# Controllable_voltage_outputs.net
KiCad netlist of a schematic drawn in Altium Designer
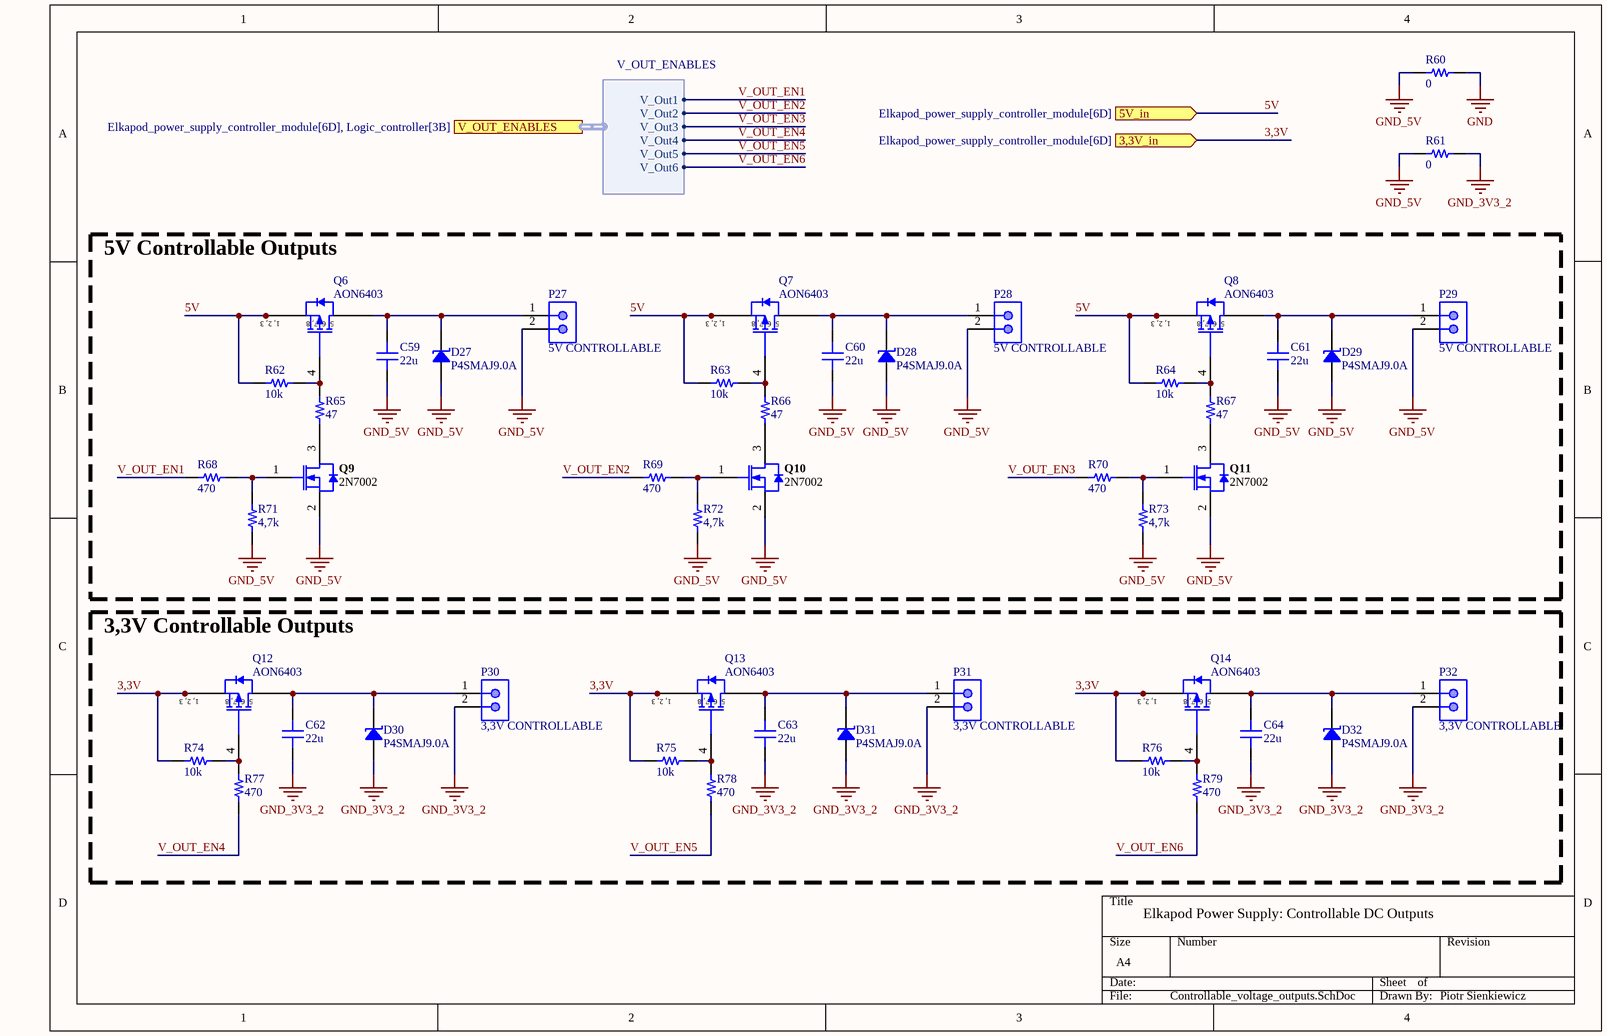
[diagram p0: Controllable_voltage_outputs.SchDoc]

(export (version "E")
  (design (tool "Eeschema 10.0.6"))
  (components
    (comp (ref "C59")
      (value "22u")
      (footprint "CAP 0805_2012")
      (description "CAP CER 22UF 25V X7R 0805")
      (fields
        (field (name "PART NUMBER") "VJ0805Y684KXQTW1BC")
        (field (name "MANUFACTURER") "Vishay Vitramon")
      )
      (libsource (lib "Celestial Altium Library - altium_library") (part "Capacitor"))
    )
    (comp (ref "C60")
      (value "22u")
      (footprint "CAP 0805_2012")
      (description "CAP CER 22UF 25V X7R 0805")
      (fields
        (field (name "PART NUMBER") "VJ0805Y684KXQTW1BC")
        (field (name "MANUFACTURER") "Vishay Vitramon")
      )
      (libsource (lib "Celestial Altium Library - altium_library") (part "Capacitor"))
    )
    (comp (ref "C61")
      (value "22u")
      (footprint "CAP 0805_2012")
      (description "CAP CER 22UF 25V X7R 0805")
      (fields
        (field (name "PART NUMBER") "VJ0805Y684KXQTW1BC")
        (field (name "MANUFACTURER") "Vishay Vitramon")
      )
      (libsource (lib "Celestial Altium Library - altium_library") (part "Capacitor"))
    )
    (comp (ref "C62")
      (value "22u")
      (footprint "CAP 0805_2012")
      (description "CAP CER 22UF 25V X7R 0805")
      (fields
        (field (name "PART NUMBER") "VJ0805Y684KXQTW1BC")
        (field (name "MANUFACTURER") "Vishay Vitramon")
      )
      (libsource (lib "Celestial Altium Library - altium_library") (part "Capacitor"))
    )
    (comp (ref "C63")
      (value "22u")
      (footprint "CAP 0805_2012")
      (description "CAP CER 22UF 25V X7R 0805")
      (fields
        (field (name "PART NUMBER") "VJ0805Y684KXQTW1BC")
        (field (name "MANUFACTURER") "Vishay Vitramon")
      )
      (libsource (lib "Celestial Altium Library - altium_library") (part "Capacitor"))
    )
    (comp (ref "C64")
      (value "22u")
      (footprint "CAP 0805_2012")
      (description "CAP CER 22UF 25V X7R 0805")
      (fields
        (field (name "PART NUMBER") "VJ0805Y684KXQTW1BC")
        (field (name "MANUFACTURER") "Vishay Vitramon")
      )
      (libsource (lib "Celestial Altium Library - altium_library") (part "Capacitor"))
    )
    (comp (ref "D27")
      (value "P4SMAJ9.0A")
      (footprint "DO214AC SMA")
      (description "TVS DIODE 9VDC DO214AC")
      (libsource (lib "Celestial Altium Library - altium_library") (part "DIODE TVS UNI"))
    )
    (comp (ref "D28")
      (value "P4SMAJ9.0A")
      (footprint "DO214AC SMA")
      (description "TVS DIODE 9VDC DO214AC")
      (libsource (lib "Celestial Altium Library - altium_library") (part "DIODE TVS UNI"))
    )
    (comp (ref "D29")
      (value "P4SMAJ9.0A")
      (footprint "DO214AC SMA")
      (description "TVS DIODE 9VDC DO214AC")
      (libsource (lib "Celestial Altium Library - altium_library") (part "DIODE TVS UNI"))
    )
    (comp (ref "D30")
      (value "P4SMAJ9.0A")
      (footprint "DO214AC SMA")
      (description "TVS DIODE 9VDC DO214AC")
      (libsource (lib "Celestial Altium Library - altium_library") (part "DIODE TVS UNI"))
    )
    (comp (ref "D31")
      (value "P4SMAJ9.0A")
      (footprint "DO214AC SMA")
      (description "TVS DIODE 9VDC DO214AC")
      (libsource (lib "Celestial Altium Library - altium_library") (part "DIODE TVS UNI"))
    )
    (comp (ref "D32")
      (value "P4SMAJ9.0A")
      (footprint "DO214AC SMA")
      (description "TVS DIODE 9VDC DO214AC")
      (libsource (lib "Celestial Altium Library - altium_library") (part "DIODE TVS UNI"))
    )
    (comp (ref "P27")
      (value "5V CONTROLLABLE")
      (footprint "MOLX-22-23-2021_V")
      (fields (field (name "PARTNUMBER") "22-23-2021"))
      (libsource (lib "Altium Content Vault") (part "CN-1P-M-R2"))
    )
    (comp (ref "P28")
      (value "5V CONTROLLABLE")
      (footprint "MOLX-22-23-2021_V")
      (fields (field (name "PARTNUMBER") "22-23-2021"))
      (libsource (lib "Altium Content Vault") (part "CN-1P-M-R2"))
    )
    (comp (ref "P29")
      (value "5V CONTROLLABLE")
      (footprint "MOLX-22-23-2021_V")
      (fields (field (name "PARTNUMBER") "22-23-2021"))
      (libsource (lib "Altium Content Vault") (part "CN-1P-M-R2"))
    )
    (comp (ref "P30")
      (value "3,3V CONTROLLABLE")
      (footprint "MOLX-22-23-2021_V")
      (fields (field (name "PARTNUMBER") "22-23-2021"))
      (libsource (lib "Altium Content Vault") (part "CN-1P-M-R2"))
    )
    (comp (ref "P31")
      (value "3,3V CONTROLLABLE")
      (footprint "MOLX-22-23-2021_V")
      (fields (field (name "PARTNUMBER") "22-23-2021"))
      (libsource (lib "Altium Content Vault") (part "CN-1P-M-R2"))
    )
    (comp (ref "P32")
      (value "3,3V CONTROLLABLE")
      (footprint "MOLX-22-23-2021_V")
      (fields (field (name "PARTNUMBER") "22-23-2021"))
      (libsource (lib "Altium Content Vault") (part "CN-1P-M-R2"))
    )
    (comp (ref "Q6")
      (value "AON6403")
      (footprint "DFN5x6")
      (description "P-MOSFET; 67A; 30V; DFN5x6")
      (libsource (lib "My_transistors") (part "AON6403"))
    )
    (comp (ref "Q7")
      (value "AON6403")
      (footprint "DFN5x6")
      (description "P-MOSFET; 67A; 30V; DFN5x6")
      (libsource (lib "My_transistors") (part "AON6403"))
    )
    (comp (ref "Q8")
      (value "AON6403")
      (footprint "DFN5x6")
      (description "P-MOSFET; 67A; 30V; DFN5x6")
      (libsource (lib "My_transistors") (part "AON6403"))
    )
    (comp (ref "Q9")
      (value "2N7002")
      (footprint "INF-PG-SOT23_M")
      (fields (field (name "MANUFACTURER") "Infineon"))
      (libsource (lib "Altium Content Vault") (part "INF-NDMOS-GSD-3"))
    )
    (comp (ref "Q10")
      (value "2N7002")
      (footprint "INF-PG-SOT23_M")
      (fields (field (name "MANUFACTURER") "Infineon"))
      (libsource (lib "Altium Content Vault") (part "INF-NDMOS-GSD-3"))
    )
    (comp (ref "Q11")
      (value "2N7002")
      (footprint "INF-PG-SOT23_M")
      (fields (field (name "MANUFACTURER") "Infineon"))
      (libsource (lib "Altium Content Vault") (part "INF-NDMOS-GSD-3"))
    )
    (comp (ref "Q12")
      (value "AON6403")
      (footprint "DFN5x6")
      (description "P-MOSFET; 67A; 30V; DFN5x6")
      (libsource (lib "My_transistors") (part "AON6403"))
    )
    (comp (ref "Q13")
      (value "AON6403")
      (footprint "DFN5x6")
      (description "P-MOSFET; 67A; 30V; DFN5x6")
      (libsource (lib "My_transistors") (part "AON6403"))
    )
    (comp (ref "Q14")
      (value "AON6403")
      (footprint "DFN5x6")
      (description "P-MOSFET; 67A; 30V; DFN5x6")
      (libsource (lib "My_transistors") (part "AON6403"))
    )
    (comp (ref "R60")
      (value "0")
      (footprint "RES 0603_1608")
      (description "RES 0 OHM 1% 0,1W 0603")
      (fields
        (field (name "PART NUMBER") "RNCS0603BKE10K0")
        (field (name "MANUFACTURER") "Stackpole Electronics Inc")
      )
      (libsource (lib "Celestial Altium Library - altium_library") (part "Resistor"))
    )
    (comp (ref "R61")
      (value "0")
      (footprint "RES 0603_1608")
      (description "RES 0 OHM 1% 0,1W 0603")
      (fields
        (field (name "PART NUMBER") "RNCS0603BKE10K0")
        (field (name "MANUFACTURER") "Stackpole Electronics Inc")
      )
      (libsource (lib "Celestial Altium Library - altium_library") (part "Resistor"))
    )
    (comp (ref "R62")
      (value "10k")
      (footprint "RES 0603_1608")
      (description "RES 10K OHM 1% 0,1W 0603")
      (fields
        (field (name "PART NUMBER") "RNCS0603BKE10K0")
        (field (name "MANUFACTURER") "Stackpole Electronics Inc")
      )
      (libsource (lib "Celestial Altium Library - altium_library") (part "Resistor"))
    )
    (comp (ref "R63")
      (value "10k")
      (footprint "RES 0603_1608")
      (description "RES 10K OHM 1% 0,1W 0603")
      (fields
        (field (name "PART NUMBER") "RNCS0603BKE10K0")
        (field (name "MANUFACTURER") "Stackpole Electronics Inc")
      )
      (libsource (lib "Celestial Altium Library - altium_library") (part "Resistor"))
    )
    (comp (ref "R64")
      (value "10k")
      (footprint "RES 0603_1608")
      (description "RES 10K OHM 1% 0,1W 0603")
      (fields
        (field (name "PART NUMBER") "RNCS0603BKE10K0")
        (field (name "MANUFACTURER") "Stackpole Electronics Inc")
      )
      (libsource (lib "Celestial Altium Library - altium_library") (part "Resistor"))
    )
    (comp (ref "R65")
      (value "47")
      (footprint "RES 0603_1608")
      (description "RES 47 OHM 1% 0,1W 0603")
      (fields
        (field (name "PART NUMBER") "RNCS0603BKE10K0")
        (field (name "MANUFACTURER") "Stackpole Electronics Inc")
      )
      (libsource (lib "Celestial Altium Library - altium_library") (part "Resistor"))
    )
    (comp (ref "R66")
      (value "47")
      (footprint "RES 0603_1608")
      (description "RES 47 OHM 1% 0,1W 0603")
      (fields
        (field (name "PART NUMBER") "RNCS0603BKE10K0")
        (field (name "MANUFACTURER") "Stackpole Electronics Inc")
      )
      (libsource (lib "Celestial Altium Library - altium_library") (part "Resistor"))
    )
    (comp (ref "R67")
      (value "47")
      (footprint "RES 0603_1608")
      (description "RES 47 OHM 1% 0,1W 0603")
      (fields
        (field (name "PART NUMBER") "RNCS0603BKE10K0")
        (field (name "MANUFACTURER") "Stackpole Electronics Inc")
      )
      (libsource (lib "Celestial Altium Library - altium_library") (part "Resistor"))
    )
    (comp (ref "R68")
      (value "470")
      (footprint "RES 0603_1608")
      (description "RES 470 OHM 1% 0,1W 0603")
      (fields
        (field (name "PART NUMBER") "RNCS0603BKE10K0")
        (field (name "MANUFACTURER") "Stackpole Electronics Inc")
      )
      (libsource (lib "Celestial Altium Library - altium_library") (part "Resistor"))
    )
    (comp (ref "R69")
      (value "470")
      (footprint "RES 0603_1608")
      (description "RES 470 OHM 1% 0,1W 0603")
      (fields
        (field (name "PART NUMBER") "RNCS0603BKE10K0")
        (field (name "MANUFACTURER") "Stackpole Electronics Inc")
      )
      (libsource (lib "Celestial Altium Library - altium_library") (part "Resistor"))
    )
    (comp (ref "R70")
      (value "470")
      (footprint "RES 0603_1608")
      (description "RES 470 OHM 1% 0,1W 0603")
      (fields
        (field (name "PART NUMBER") "RNCS0603BKE10K0")
        (field (name "MANUFACTURER") "Stackpole Electronics Inc")
      )
      (libsource (lib "Celestial Altium Library - altium_library") (part "Resistor"))
    )
    (comp (ref "R71")
      (value "4,7k")
      (footprint "RES 0603_1608")
      (description "RES 4,7K OHM 1% 0,1W 0603")
      (fields
        (field (name "PART NUMBER") "RNCS0603BKE10K0")
        (field (name "MANUFACTURER") "Stackpole Electronics Inc")
      )
      (libsource (lib "Celestial Altium Library - altium_library") (part "Resistor"))
    )
    (comp (ref "R72")
      (value "4,7k")
      (footprint "RES 0603_1608")
      (description "RES 4,7K OHM 1% 0,1W 0603")
      (fields
        (field (name "PART NUMBER") "RNCS0603BKE10K0")
        (field (name "MANUFACTURER") "Stackpole Electronics Inc")
      )
      (libsource (lib "Celestial Altium Library - altium_library") (part "Resistor"))
    )
    (comp (ref "R73")
      (value "4,7k")
      (footprint "RES 0603_1608")
      (description "RES 4,7K OHM 1% 0,1W 0603")
      (fields
        (field (name "PART NUMBER") "RNCS0603BKE10K0")
        (field (name "MANUFACTURER") "Stackpole Electronics Inc")
      )
      (libsource (lib "Celestial Altium Library - altium_library") (part "Resistor"))
    )
    (comp (ref "R74")
      (value "10k")
      (footprint "RES 0603_1608")
      (description "RES 10K OHM 1% 0,1W 0603")
      (fields
        (field (name "PART NUMBER") "RNCS0603BKE10K0")
        (field (name "MANUFACTURER") "Stackpole Electronics Inc")
      )
      (libsource (lib "Celestial Altium Library - altium_library") (part "Resistor"))
    )
    (comp (ref "R75")
      (value "10k")
      (footprint "RES 0603_1608")
      (description "RES 10K OHM 1% 0,1W 0603")
      (fields
        (field (name "PART NUMBER") "RNCS0603BKE10K0")
        (field (name "MANUFACTURER") "Stackpole Electronics Inc")
      )
      (libsource (lib "Celestial Altium Library - altium_library") (part "Resistor"))
    )
    (comp (ref "R76")
      (value "10k")
      (footprint "RES 0603_1608")
      (description "RES 10K OHM 1% 0,1W 0603")
      (fields
        (field (name "PART NUMBER") "RNCS0603BKE10K0")
        (field (name "MANUFACTURER") "Stackpole Electronics Inc")
      )
      (libsource (lib "Celestial Altium Library - altium_library") (part "Resistor"))
    )
    (comp (ref "R77")
      (value "470")
      (footprint "RES 0603_1608")
      (description "RES 470 OHM 1% 0,1W 0603")
      (fields
        (field (name "PART NUMBER") "RNCS0603BKE10K0")
        (field (name "MANUFACTURER") "Stackpole Electronics Inc")
      )
      (libsource (lib "Celestial Altium Library - altium_library") (part "Resistor"))
    )
    (comp (ref "R78")
      (value "470")
      (footprint "RES 0603_1608")
      (description "RES 470 OHM 1% 0,1W 0603")
      (fields
        (field (name "PART NUMBER") "RNCS0603BKE10K0")
        (field (name "MANUFACTURER") "Stackpole Electronics Inc")
      )
      (libsource (lib "Celestial Altium Library - altium_library") (part "Resistor"))
    )
    (comp (ref "R79")
      (value "470")
      (footprint "RES 0603_1608")
      (description "RES 470 OHM 1% 0,1W 0603")
      (fields
        (field (name "PART NUMBER") "RNCS0603BKE10K0")
        (field (name "MANUFACTURER") "Stackpole Electronics Inc")
      )
      (libsource (lib "Celestial Altium Library - altium_library") (part "Resistor"))
    )
  )
  (nets
    (net (code "2") (name "/3,3V") (class "Default")
      (node (ref "Q12") (pin "1") (pinfunction "S_1") (pintype "passive"))
      (node (ref "Q12") (pin "2") (pinfunction "S_2") (pintype "passive"))
      (node (ref "Q12") (pin "3") (pinfunction "S_3") (pintype "passive"))
      (node (ref "Q13") (pin "1") (pinfunction "S_1") (pintype "passive"))
      (node (ref "Q13") (pin "2") (pinfunction "S_2") (pintype "passive"))
      (node (ref "Q13") (pin "3") (pinfunction "S_3") (pintype "passive"))
      (node (ref "Q14") (pin "1") (pinfunction "S_1") (pintype "passive"))
      (node (ref "Q14") (pin "2") (pinfunction "S_2") (pintype "passive"))
      (node (ref "Q14") (pin "3") (pinfunction "S_3") (pintype "passive"))
      (node (ref "R74") (pin "1") (pinfunction "1_1") (pintype "passive"))
      (node (ref "R75") (pin "1") (pinfunction "1_1") (pintype "passive"))
      (node (ref "R76") (pin "1") (pinfunction "1_1") (pintype "passive"))
    )
    (net (code "3") (name "/5V") (class "Default")
      (node (ref "Q6") (pin "1") (pinfunction "S_1") (pintype "passive"))
      (node (ref "Q6") (pin "2") (pinfunction "S_2") (pintype "passive"))
      (node (ref "Q6") (pin "3") (pinfunction "S_3") (pintype "passive"))
      (node (ref "Q7") (pin "1") (pinfunction "S_1") (pintype "passive"))
      (node (ref "Q7") (pin "2") (pinfunction "S_2") (pintype "passive"))
      (node (ref "Q7") (pin "3") (pinfunction "S_3") (pintype "passive"))
      (node (ref "Q8") (pin "1") (pinfunction "S_1") (pintype "passive"))
      (node (ref "Q8") (pin "2") (pinfunction "S_2") (pintype "passive"))
      (node (ref "Q8") (pin "3") (pinfunction "S_3") (pintype "passive"))
      (node (ref "R62") (pin "1") (pinfunction "1_1") (pintype "passive"))
      (node (ref "R63") (pin "1") (pinfunction "1_1") (pintype "passive"))
      (node (ref "R64") (pin "1") (pinfunction "1_1") (pintype "passive"))
    )
    (net (code "4") (name "/V_OUT_EN1") (class "Default")
      (node (ref "R68") (pin "2") (pinfunction "2_2") (pintype "passive"))
    )
    (net (code "5") (name "/V_OUT_EN2") (class "Default")
      (node (ref "R69") (pin "2") (pinfunction "2_2") (pintype "passive"))
    )
    (net (code "6") (name "/V_OUT_EN3") (class "Default")
      (node (ref "R70") (pin "2") (pinfunction "2_2") (pintype "passive"))
    )
    (net (code "7") (name "/V_OUT_EN4") (class "Default")
      (node (ref "R77") (pin "2") (pinfunction "2_2") (pintype "passive"))
    )
    (net (code "8") (name "/V_OUT_EN5") (class "Default")
      (node (ref "R78") (pin "2") (pinfunction "2_2") (pintype "passive"))
    )
    (net (code "9") (name "/V_OUT_EN6") (class "Default")
      (node (ref "R79") (pin "2") (pinfunction "2_2") (pintype "passive"))
    )
    (net (code "11") (name "GND") (class "Default")
      (node (ref "R60") (pin "2") (pinfunction "2_2") (pintype "passive"))
    )
    (net (code "12") (name "GND_3V3_2") (class "Default")
      (node (ref "C62") (pin "1") (pinfunction "1_1") (pintype "passive"))
      (node (ref "C63") (pin "1") (pinfunction "1_1") (pintype "passive"))
      (node (ref "C64") (pin "1") (pinfunction "1_1") (pintype "passive"))
      (node (ref "D30") (pin "1") (pinfunction "1_1") (pintype "passive"))
      (node (ref "D31") (pin "1") (pinfunction "1_1") (pintype "passive"))
      (node (ref "D32") (pin "1") (pinfunction "1_1") (pintype "passive"))
      (node (ref "P30") (pin "2") (pinfunction "2_2") (pintype "passive"))
      (node (ref "P31") (pin "2") (pinfunction "2_2") (pintype "passive"))
      (node (ref "P32") (pin "2") (pinfunction "2_2") (pintype "passive"))
      (node (ref "R61") (pin "2") (pinfunction "2_2") (pintype "passive"))
    )
    (net (code "13") (name "GND_5V") (class "Default")
      (node (ref "C59") (pin "1") (pinfunction "1_1") (pintype "passive"))
      (node (ref "C60") (pin "1") (pinfunction "1_1") (pintype "passive"))
      (node (ref "C61") (pin "1") (pinfunction "1_1") (pintype "passive"))
      (node (ref "D27") (pin "1") (pinfunction "1_1") (pintype "passive"))
      (node (ref "D28") (pin "1") (pinfunction "1_1") (pintype "passive"))
      (node (ref "D29") (pin "1") (pinfunction "1_1") (pintype "passive"))
      (node (ref "P27") (pin "2") (pinfunction "2_2") (pintype "passive"))
      (node (ref "P28") (pin "2") (pinfunction "2_2") (pintype "passive"))
      (node (ref "P29") (pin "2") (pinfunction "2_2") (pintype "passive"))
      (node (ref "Q10") (pin "2") (pinfunction "SOURCE_2") (pintype "passive"))
      (node (ref "Q11") (pin "2") (pinfunction "SOURCE_2") (pintype "passive"))
      (node (ref "Q9") (pin "2") (pinfunction "SOURCE_2") (pintype "passive"))
      (node (ref "R60") (pin "1") (pinfunction "1_1") (pintype "passive"))
      (node (ref "R61") (pin "1") (pinfunction "1_1") (pintype "passive"))
      (node (ref "R71") (pin "2") (pinfunction "2_2") (pintype "passive"))
      (node (ref "R72") (pin "2") (pinfunction "2_2") (pintype "passive"))
      (node (ref "R73") (pin "2") (pinfunction "2_2") (pintype "passive"))
    )
    (net (code "14") (name "Net-(Q6-D)") (class "Default")
      (node (ref "C59") (pin "2") (pinfunction "2_2") (pintype "passive"))
      (node (ref "D27") (pin "2") (pinfunction "2_2") (pintype "passive"))
      (node (ref "P27") (pin "1") (pinfunction "1_1") (pintype "passive"))
      (node (ref "Q6") (pin "5") (pinfunction "D_5") (pintype "passive"))
    )
    (net (code "15") (name "Net-(Q6-G)") (class "Default")
      (node (ref "Q6") (pin "4") (pinfunction "G_4") (pintype "passive"))
      (node (ref "R62") (pin "2") (pinfunction "2_2") (pintype "passive"))
      (node (ref "R65") (pin "1") (pinfunction "1_1") (pintype "passive"))
    )
    (net (code "16") (name "Net-(Q7-D)") (class "Default")
      (node (ref "C60") (pin "2") (pinfunction "2_2") (pintype "passive"))
      (node (ref "D28") (pin "2") (pinfunction "2_2") (pintype "passive"))
      (node (ref "P28") (pin "1") (pinfunction "1_1") (pintype "passive"))
      (node (ref "Q7") (pin "5") (pinfunction "D_5") (pintype "passive"))
    )
    (net (code "17") (name "Net-(Q7-G)") (class "Default")
      (node (ref "Q7") (pin "4") (pinfunction "G_4") (pintype "passive"))
      (node (ref "R63") (pin "2") (pinfunction "2_2") (pintype "passive"))
      (node (ref "R66") (pin "1") (pinfunction "1_1") (pintype "passive"))
    )
    (net (code "18") (name "Net-(Q8-D)") (class "Default")
      (node (ref "C61") (pin "2") (pinfunction "2_2") (pintype "passive"))
      (node (ref "D29") (pin "2") (pinfunction "2_2") (pintype "passive"))
      (node (ref "P29") (pin "1") (pinfunction "1_1") (pintype "passive"))
      (node (ref "Q8") (pin "5") (pinfunction "D_5") (pintype "passive"))
    )
    (net (code "19") (name "Net-(Q8-G)") (class "Default")
      (node (ref "Q8") (pin "4") (pinfunction "G_4") (pintype "passive"))
      (node (ref "R64") (pin "2") (pinfunction "2_2") (pintype "passive"))
      (node (ref "R67") (pin "1") (pinfunction "1_1") (pintype "passive"))
    )
    (net (code "20") (name "Net-(Q9-DRAIN)") (class "Default")
      (node (ref "Q9") (pin "3") (pinfunction "DRAIN_3") (pintype "passive"))
      (node (ref "R65") (pin "2") (pinfunction "2_2") (pintype "passive"))
    )
    (net (code "21") (name "Net-(Q9-GATE)") (class "Default")
      (node (ref "Q9") (pin "1") (pinfunction "GATE_1") (pintype "passive"))
      (node (ref "R68") (pin "1") (pinfunction "1_1") (pintype "passive"))
      (node (ref "R71") (pin "1") (pinfunction "1_1") (pintype "passive"))
    )
    (net (code "22") (name "Net-(Q10-DRAIN)") (class "Default")
      (node (ref "Q10") (pin "3") (pinfunction "DRAIN_3") (pintype "passive"))
      (node (ref "R66") (pin "2") (pinfunction "2_2") (pintype "passive"))
    )
    (net (code "23") (name "Net-(Q10-GATE)") (class "Default")
      (node (ref "Q10") (pin "1") (pinfunction "GATE_1") (pintype "passive"))
      (node (ref "R69") (pin "1") (pinfunction "1_1") (pintype "passive"))
      (node (ref "R72") (pin "1") (pinfunction "1_1") (pintype "passive"))
    )
    (net (code "24") (name "Net-(Q11-DRAIN)") (class "Default")
      (node (ref "Q11") (pin "3") (pinfunction "DRAIN_3") (pintype "passive"))
      (node (ref "R67") (pin "2") (pinfunction "2_2") (pintype "passive"))
    )
    (net (code "25") (name "Net-(Q11-GATE)") (class "Default")
      (node (ref "Q11") (pin "1") (pinfunction "GATE_1") (pintype "passive"))
      (node (ref "R70") (pin "1") (pinfunction "1_1") (pintype "passive"))
      (node (ref "R73") (pin "1") (pinfunction "1_1") (pintype "passive"))
    )
    (net (code "26") (name "Net-(Q12-D)") (class "Default")
      (node (ref "C62") (pin "2") (pinfunction "2_2") (pintype "passive"))
      (node (ref "D30") (pin "2") (pinfunction "2_2") (pintype "passive"))
      (node (ref "P30") (pin "1") (pinfunction "1_1") (pintype "passive"))
      (node (ref "Q12") (pin "5") (pinfunction "D_5") (pintype "passive"))
    )
    (net (code "27") (name "Net-(Q12-G)") (class "Default")
      (node (ref "Q12") (pin "4") (pinfunction "G_4") (pintype "passive"))
      (node (ref "R74") (pin "2") (pinfunction "2_2") (pintype "passive"))
      (node (ref "R77") (pin "1") (pinfunction "1_1") (pintype "passive"))
    )
    (net (code "28") (name "Net-(Q13-D)") (class "Default")
      (node (ref "C63") (pin "2") (pinfunction "2_2") (pintype "passive"))
      (node (ref "D31") (pin "2") (pinfunction "2_2") (pintype "passive"))
      (node (ref "P31") (pin "1") (pinfunction "1_1") (pintype "passive"))
      (node (ref "Q13") (pin "5") (pinfunction "D_5") (pintype "passive"))
    )
    (net (code "29") (name "Net-(Q13-G)") (class "Default")
      (node (ref "Q13") (pin "4") (pinfunction "G_4") (pintype "passive"))
      (node (ref "R75") (pin "2") (pinfunction "2_2") (pintype "passive"))
      (node (ref "R78") (pin "1") (pinfunction "1_1") (pintype "passive"))
    )
    (net (code "30") (name "Net-(Q14-D)") (class "Default")
      (node (ref "C64") (pin "2") (pinfunction "2_2") (pintype "passive"))
      (node (ref "D32") (pin "2") (pinfunction "2_2") (pintype "passive"))
      (node (ref "P32") (pin "1") (pinfunction "1_1") (pintype "passive"))
      (node (ref "Q14") (pin "5") (pinfunction "D_5") (pintype "passive"))
    )
    (net (code "31") (name "Net-(Q14-G)") (class "Default")
      (node (ref "Q14") (pin "4") (pinfunction "G_4") (pintype "passive"))
      (node (ref "R76") (pin "2") (pinfunction "2_2") (pintype "passive"))
      (node (ref "R79") (pin "1") (pinfunction "1_1") (pintype "passive"))
    )
  )
)
